# TouScruino-v2_1.net
KiCad netlist of a schematic drawn in EAGLE
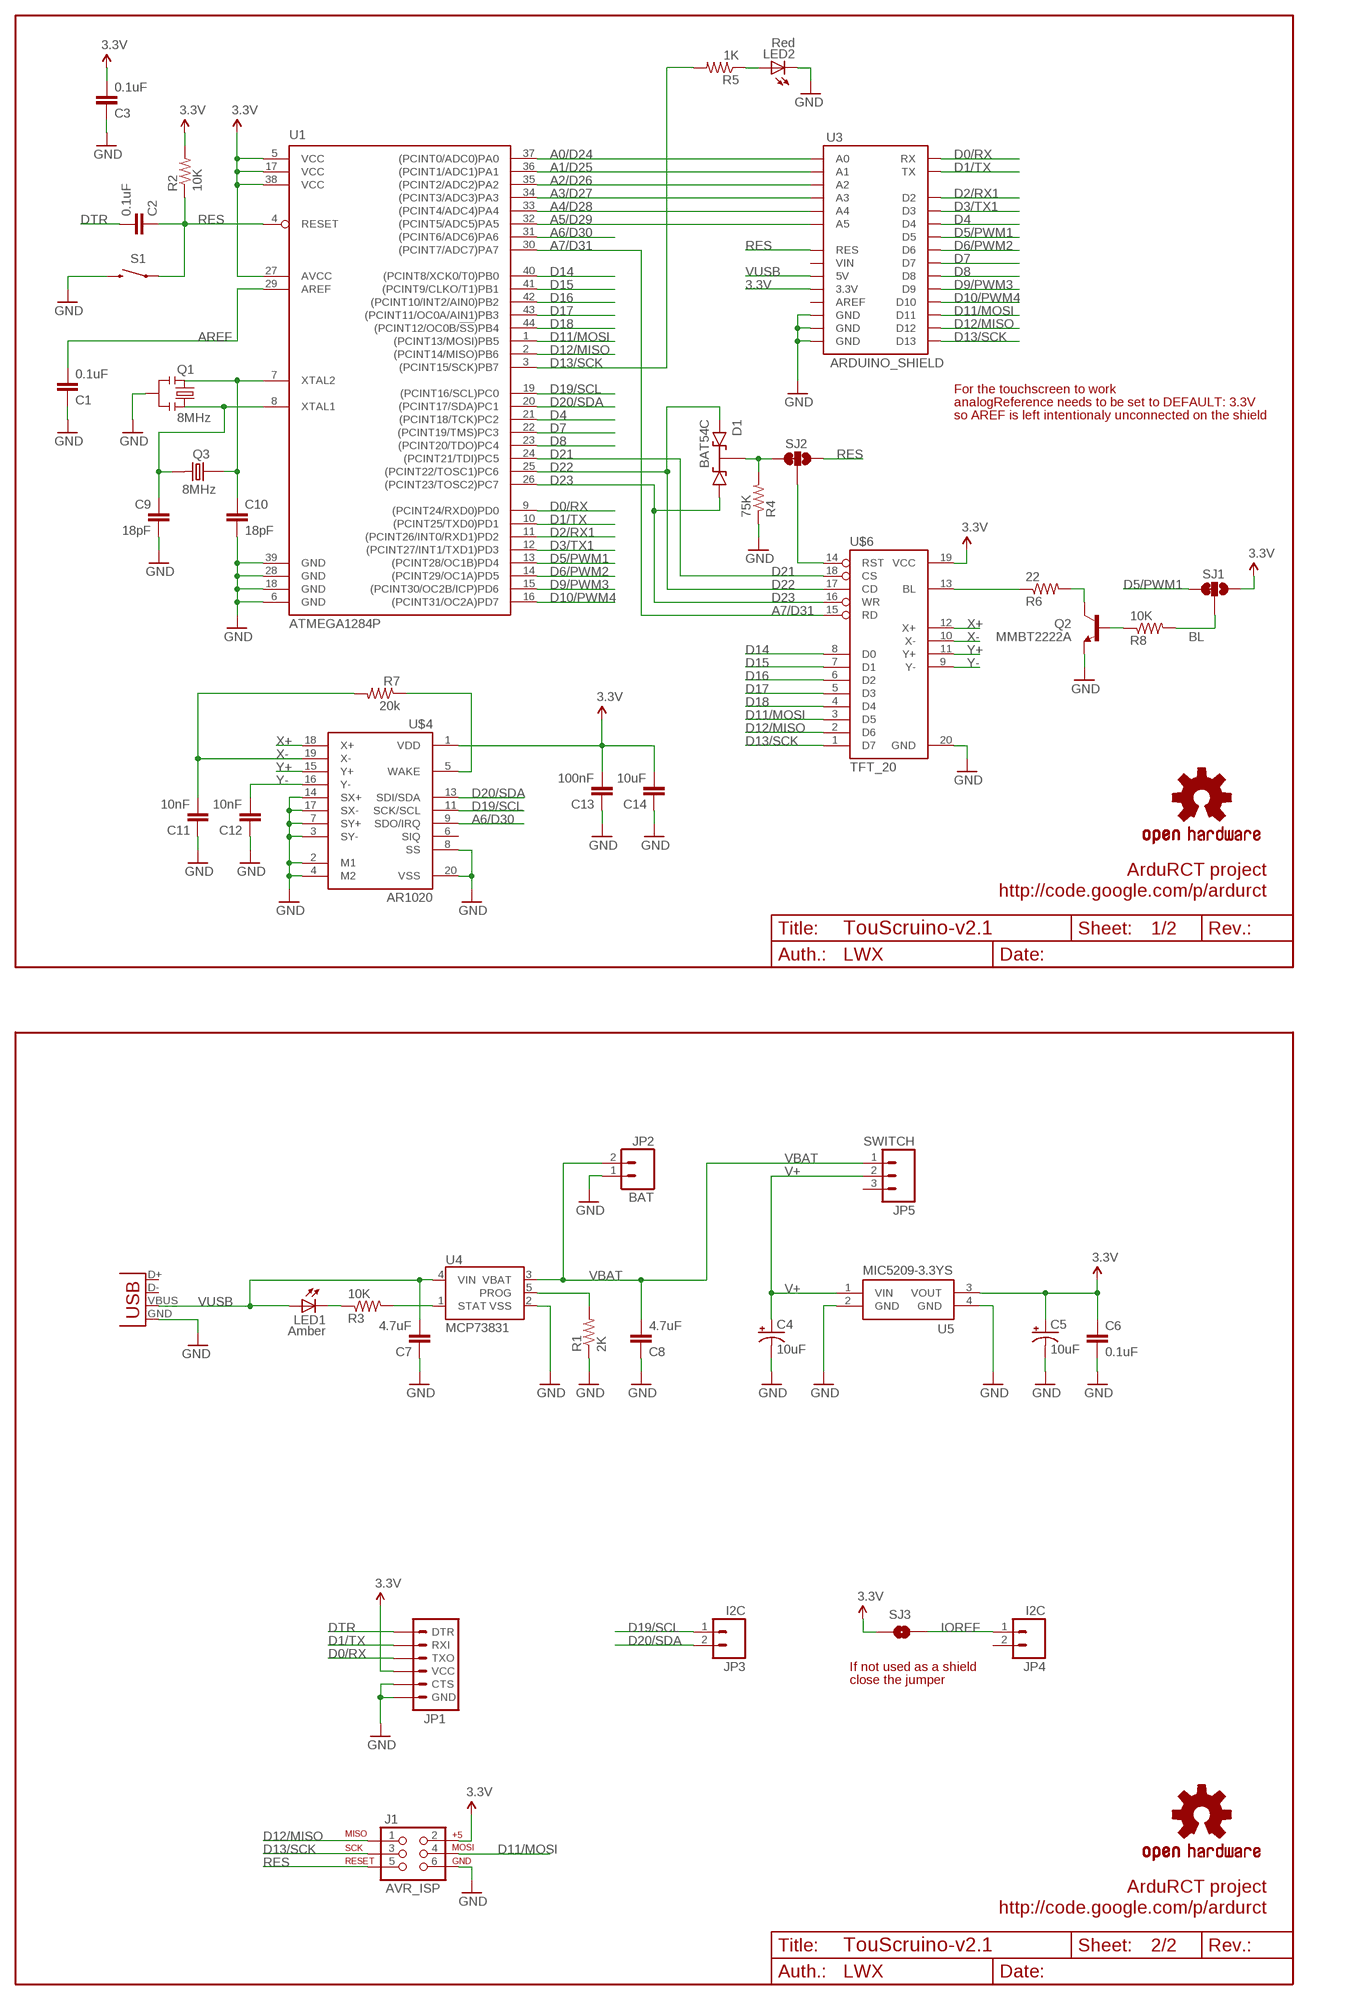
[diagram p0: schematic, sheet 1]

(export (version "E")
  (design (tool "Eeschema 10.0.6"))
  (components
    (comp (ref "C1")
      (value "0.1uF")
      (footprint "eagle-import:0805")
      (libsource (lib "eagle-import") (part "CAP0805"))
    )
    (comp (ref "C2")
      (value "0.1uF")
      (footprint "eagle-import:0805")
      (libsource (lib "eagle-import") (part "CAP0805"))
    )
    (comp (ref "C3")
      (value "0.1uF")
      (footprint "eagle-import:0805")
      (libsource (lib "eagle-import") (part "CAP0805"))
    )
    (comp (ref "C4")
      (value "10uF")
      (footprint "eagle-import:EIA3216")
      (libsource (lib "eagle-import") (part "CAP_POL1206"))
    )
    (comp (ref "C5")
      (value "10uF")
      (footprint "eagle-import:EIA3216")
      (libsource (lib "eagle-import") (part "CAP_POL1206"))
    )
    (comp (ref "C6")
      (value "0.1uF")
      (footprint "eagle-import:0805")
      (libsource (lib "eagle-import") (part "CAP0805"))
    )
    (comp (ref "C7")
      (value "4.7uF")
      (footprint "eagle-import:0805")
      (libsource (lib "eagle-import") (part "CAP0805"))
    )
    (comp (ref "C8")
      (value "4.7uF")
      (footprint "eagle-import:0805")
      (libsource (lib "eagle-import") (part "CAP0805"))
    )
    (comp (ref "C9")
      (value "18pF")
      (footprint "eagle-import:0603-CAP")
      (libsource (lib "eagle-import") (part "CAP0603-CAP"))
    )
    (comp (ref "C10")
      (value "18pF")
      (footprint "eagle-import:0603-CAP")
      (libsource (lib "eagle-import") (part "CAP0603-CAP"))
    )
    (comp (ref "C11")
      (value "10nF")
      (footprint "eagle-import:0805")
      (libsource (lib "eagle-import") (part "CAP0805"))
    )
    (comp (ref "C12")
      (value "10nF")
      (footprint "eagle-import:0805")
      (libsource (lib "eagle-import") (part "CAP0805"))
    )
    (comp (ref "C13")
      (value "100nF")
      (footprint "eagle-import:0805")
      (libsource (lib "eagle-import") (part "CAP0805"))
    )
    (comp (ref "C14")
      (value "10uF")
      (footprint "eagle-import:0805")
      (libsource (lib "eagle-import") (part "CAP0805"))
    )
    (comp (ref "D1")
      (value "BAT54C")
      (footprint "eagle-import:SOT23-3")
      (libsource (lib "eagle-import") (part "BAT54C"))
    )
    (comp (ref "J1")
      (value "AVR_ISP")
      (footprint "eagle-import:2X3")
      (libsource (lib "eagle-import") (part "AVR_SPI_PRG_6PTH"))
    )
    (comp (ref "JP1")
      (value "ARDUINO_SERIAL_PROGRAMPTH")
      (footprint "eagle-import:1X06")
      (libsource (lib "eagle-import") (part "ARDUINO_SERIAL_PROGRAMPTH"))
    )
    (comp (ref "JP2")
      (value "BAT")
      (footprint "eagle-import:JST-2-SMD")
      (libsource (lib "eagle-import") (part "M02-JST-2MM-SMT"))
    )
    (comp (ref "JP3")
      (value "I2C")
      (footprint "eagle-import:1X02")
      (libsource (lib "eagle-import") (part "M02"))
    )
    (comp (ref "JP4")
      (value "I2C")
      (footprint "eagle-import:1X02")
      (libsource (lib "eagle-import") (part "M02"))
    )
    (comp (ref "JP5")
      (value "SWITCH")
      (footprint "eagle-import:1X3_LONGPAD")
      (libsource (lib "eagle-import") (part "M03"))
    )
    (comp (ref "LED1")
      (value "Amber")
      (footprint "eagle-import:LED")
      (libsource (lib "eagle-import") (part "LED"))
    )
    (comp (ref "LED2")
      (value "Red")
      (footprint "eagle-import:LED-0805")
      (libsource (lib "eagle-import") (part "LED805"))
    )
    (comp (ref "Q1")
      (value "8MHz")
      (footprint "eagle-import:RESONATOR-SMD")
      (libsource (lib "eagle-import") (part "RESONATORSMD"))
    )
    (comp (ref "Q2")
      (value "MMBT2222A")
      (footprint "eagle-import:SOT23-3")
      (libsource (lib "eagle-import") (part "TRANSISTOR_NPNSOT23-3"))
    )
    (comp (ref "Q3")
      (value "8MHz")
      (footprint "eagle-import:CRYSTAL_5X3.2")
      (libsource (lib "eagle-import") (part "CRYSTAL_5X3.2"))
    )
    (comp (ref "R1")
      (value "2K")
      (footprint "eagle-import:0805")
      (libsource (lib "eagle-import") (part "RESISTOR0805-RES"))
    )
    (comp (ref "R2")
      (value "10K")
      (footprint "eagle-import:0805")
      (libsource (lib "eagle-import") (part "RESISTOR0805-RES"))
    )
    (comp (ref "R3")
      (value "10K")
      (footprint "eagle-import:0805")
      (libsource (lib "eagle-import") (part "RESISTOR0805-RES"))
    )
    (comp (ref "R4")
      (value "75K")
      (footprint "eagle-import:0805")
      (libsource (lib "eagle-import") (part "RESISTOR0805-RES"))
    )
    (comp (ref "R5")
      (value "1K")
      (footprint "eagle-import:0805")
      (libsource (lib "eagle-import") (part "RESISTOR0805-RES"))
    )
    (comp (ref "R6")
      (value "22")
      (footprint "eagle-import:0805")
      (libsource (lib "eagle-import") (part "RESISTOR0805-RES"))
    )
    (comp (ref "R7")
      (value "20k")
      (footprint "eagle-import:0805")
      (libsource (lib "eagle-import") (part "RESISTOR0805-RES"))
    )
    (comp (ref "R8")
      (value "10K")
      (footprint "eagle-import:0805")
      (libsource (lib "eagle-import") (part "RESISTOR0805-RES"))
    )
    (comp (ref "S1")
      (value "SWITCH-MOMENTARY-2SMD")
      (footprint "eagle-import:TACTILE_SWITCH_SMD")
      (libsource (lib "eagle-import") (part "SWITCH-MOMENTARY-2SMD"))
    )
    (comp (ref "SJ1")
      (value "SJ_2WAYS_1-2")
      (footprint "eagle-import:SJ_2WAYS_1-2_S")
      (libsource (lib "eagle-import") (part "SJ_2WAYS_1-2"))
    )
    (comp (ref "SJ2")
      (value "SJ_2WAYS_1-2")
      (footprint "eagle-import:SJ_2WAYS_1-2_S")
      (libsource (lib "eagle-import") (part "SJ_2WAYS_1-2"))
    )
    (comp (ref "SJ3")
      (value "SOLDERJUMPERNO")
      (footprint "eagle-import:SJ_2S-NO")
      (libsource (lib "eagle-import") (part "SOLDERJUMPERNO"))
    )
    (comp (ref "U$3")
      (value "OSHW-LOGOM")
      (footprint "eagle-import:OSHW-LOGO-M")
      (libsource (lib "eagle-import") (part "OSHW-LOGOM"))
    )
    (comp (ref "U$4")
      (value "AR1020")
      (footprint "eagle-import:SSOP20")
      (libsource (lib "eagle-import") (part "AR1020"))
    )
    (comp (ref "U$5")
      (value "OSHW-LOGOM")
      (footprint "eagle-import:OSHW-LOGO-M")
      (libsource (lib "eagle-import") (part "OSHW-LOGOM"))
    )
    (comp (ref "U$6")
      (value "TFT_20")
      (footprint "eagle-import:1X20")
      (libsource (lib "eagle-import") (part "TFT_20"))
    )
    (comp (ref "U1")
      (value "ATMEGA1284P")
      (footprint "eagle-import:TQFP44")
      (libsource (lib "eagle-import") (part "ATMEGA324A"))
    )
    (comp (ref "U3")
      (value "ARDUINO_SHIELD")
      (footprint "eagle-import:ARDUINO_SHIELD")
      (libsource (lib "eagle-import") (part "ARDUINO_SHIELD"))
    )
    (comp (ref "U4")
      (value "MCP73831")
      (footprint "eagle-import:SOT23-5")
      (libsource (lib "eagle-import") (part "MCP73831"))
    )
    (comp (ref "U5")
      (value "MIC5209-3.3YS")
      (footprint "eagle-import:SOT223")
      (libsource (lib "eagle-import") (part "MIC5209"))
    )
    (comp (ref "X2")
      (value "USB-MICROB")
      (footprint "eagle-import:USB-MICROB")
      (libsource (lib "eagle-import") (part "USB-MICROB"))
    )
  )
  (nets
    (net (code "1") (name "/A0{slash}D24") (class "Default")
      (node (ref "U1") (pin "37") (pinfunction "(PCINT0/ADC0)PA0_37") (pintype "bidirectional"))
      (node (ref "U3") (pin "A0") (pinfunction "A0_A0") (pintype "bidirectional"))
    )
    (net (code "2") (name "/A1{slash}D25") (class "Default")
      (node (ref "U1") (pin "36") (pinfunction "(PCINT1/ADC1)PA1_36") (pintype "bidirectional"))
      (node (ref "U3") (pin "A1") (pinfunction "A1_A1") (pintype "bidirectional"))
    )
    (net (code "3") (name "/A2{slash}D26") (class "Default")
      (node (ref "U1") (pin "35") (pinfunction "(PCINT2/ADC2)PA2_35") (pintype "bidirectional"))
      (node (ref "U3") (pin "A2") (pinfunction "A2_A2") (pintype "bidirectional"))
    )
    (net (code "4") (name "/A3{slash}D27") (class "Default")
      (node (ref "U1") (pin "34") (pinfunction "(PCINT3/ADC3)PA3_34") (pintype "bidirectional"))
      (node (ref "U3") (pin "A3") (pinfunction "A3_A3") (pintype "bidirectional"))
    )
    (net (code "5") (name "/A4{slash}D28") (class "Default")
      (node (ref "U1") (pin "33") (pinfunction "(PCINT4/ADC4)PA4_33") (pintype "bidirectional"))
      (node (ref "U3") (pin "A4") (pinfunction "A4_A4") (pintype "bidirectional"))
    )
    (net (code "6") (name "/A5{slash}D29") (class "Default")
      (node (ref "U1") (pin "32") (pinfunction "(PCINT5/ADC5)PA5_32") (pintype "bidirectional"))
      (node (ref "U3") (pin "A5") (pinfunction "A5_A5") (pintype "bidirectional"))
    )
    (net (code "7") (name "/A6{slash}D30") (class "Default")
      (node (ref "U$4") (pin "9") (pinfunction "SDO/IRQ_9") (pintype "bidirectional"))
      (node (ref "U1") (pin "31") (pinfunction "(PCINT6/ADC6)PA6_31") (pintype "bidirectional"))
    )
    (net (code "8") (name "/A7{slash}D31") (class "Default")
      (node (ref "U$6") (pin "15") (pinfunction "RD_15") (pintype "bidirectional"))
      (node (ref "U1") (pin "30") (pinfunction "(PCINT7/ADC7)PA7_30") (pintype "bidirectional"))
    )
    (net (code "9") (name "/AREF") (class "Default")
      (node (ref "C1") (pin "2") (pinfunction "2_2") (pintype "passive"))
      (node (ref "U1") (pin "29") (pinfunction "AREF_29") (pintype "passive"))
    )
    (net (code "10") (name "/BL") (class "Default")
      (node (ref "R8") (pin "2") (pinfunction "2_2") (pintype "passive"))
      (node (ref "SJ1") (pin "2") (pinfunction "2_2") (pintype "passive"))
    )
    (net (code "11") (name "/D0{slash}RX") (class "Default")
      (node (ref "JP1") (pin "3") (pinfunction "TXO_3") (pintype "passive"))
      (node (ref "U1") (pin "9") (pinfunction "(PCINT24/RXD0)PD0_9") (pintype "bidirectional"))
      (node (ref "U3") (pin "RX") (pinfunction "RX_RX") (pintype "bidirectional"))
    )
    (net (code "12") (name "/D1{slash}TX") (class "Default")
      (node (ref "JP1") (pin "2") (pinfunction "RXI_2") (pintype "passive"))
      (node (ref "U1") (pin "10") (pinfunction "(PCINT25/TXD0)PD1_10") (pintype "bidirectional"))
      (node (ref "U3") (pin "TX") (pinfunction "TX_TX") (pintype "bidirectional"))
    )
    (net (code "13") (name "/D2{slash}RX1") (class "Default")
      (node (ref "U1") (pin "11") (pinfunction "(PCINT26/INT0/RXD1)PD2_11") (pintype "bidirectional"))
      (node (ref "U3") (pin "D2") (pinfunction "D2_D2") (pintype "bidirectional"))
    )
    (net (code "14") (name "/D3{slash}TX1") (class "Default")
      (node (ref "U1") (pin "12") (pinfunction "(PCINT27/INT1/TXD1)PD3_12") (pintype "bidirectional"))
      (node (ref "U3") (pin "D3") (pinfunction "D3_D3") (pintype "bidirectional"))
    )
    (net (code "15") (name "/D4") (class "Default")
      (node (ref "U1") (pin "21") (pinfunction "(PCINT18/TCK)PC2_21") (pintype "output"))
      (node (ref "U3") (pin "D4") (pinfunction "D4_D4") (pintype "bidirectional"))
    )
    (net (code "16") (name "/D5{slash}PWM1") (class "Default")
      (node (ref "SJ1") (pin "1") (pinfunction "1_1") (pintype "passive"))
      (node (ref "U1") (pin "13") (pinfunction "(PCINT28/OC1B)PD4_13") (pintype "bidirectional"))
      (node (ref "U3") (pin "D5") (pinfunction "D5_D5") (pintype "bidirectional"))
    )
    (net (code "17") (name "/D6{slash}PWM2") (class "Default")
      (node (ref "U1") (pin "14") (pinfunction "(PCINT29/OC1A)PD5_14") (pintype "bidirectional"))
      (node (ref "U3") (pin "D6") (pinfunction "D6_D6") (pintype "bidirectional"))
    )
    (net (code "18") (name "/D7") (class "Default")
      (node (ref "U1") (pin "22") (pinfunction "(PCINT19/TMS)PC3_22") (pintype "output"))
      (node (ref "U3") (pin "D7") (pinfunction "D7_D7") (pintype "bidirectional"))
    )
    (net (code "19") (name "/D8") (class "Default")
      (node (ref "U1") (pin "23") (pinfunction "(PCINT20/TDO)PC4_23") (pintype "output"))
      (node (ref "U3") (pin "D8") (pinfunction "D8_D8") (pintype "bidirectional"))
    )
    (net (code "20") (name "/D9{slash}PWM3") (class "Default")
      (node (ref "U1") (pin "15") (pinfunction "(PCINT30/OC2B/ICP)PD6_15") (pintype "bidirectional"))
      (node (ref "U3") (pin "D9") (pinfunction "D9_D9") (pintype "bidirectional"))
    )
    (net (code "21") (name "/D10{slash}PWM4") (class "Default")
      (node (ref "U1") (pin "16") (pinfunction "(PCINT31/OC2A)PD7_16") (pintype "bidirectional"))
      (node (ref "U3") (pin "D10") (pinfunction "D10_D10") (pintype "bidirectional"))
    )
    (net (code "22") (name "/D11{slash}MOSI") (class "Default")
      (node (ref "J1") (pin "4") (pinfunction "4_4") (pintype "passive"))
      (node (ref "U$6") (pin "3") (pinfunction "D5_3") (pintype "bidirectional"))
      (node (ref "U1") (pin "1") (pinfunction "(PCINT13/MOSI)PB5_1") (pintype "bidirectional"))
      (node (ref "U3") (pin "D11") (pinfunction "D11_D11") (pintype "bidirectional"))
    )
    (net (code "23") (name "/D12{slash}MISO") (class "Default")
      (node (ref "J1") (pin "1") (pinfunction "1_1") (pintype "passive"))
      (node (ref "U$6") (pin "2") (pinfunction "D6_2") (pintype "bidirectional"))
      (node (ref "U1") (pin "2") (pinfunction "(PCINT14/MISO)PB6_2") (pintype "bidirectional"))
      (node (ref "U3") (pin "D12") (pinfunction "D12_D12") (pintype "bidirectional"))
    )
    (net (code "24") (name "/D13{slash}SCK") (class "Default")
      (node (ref "J1") (pin "3") (pinfunction "3_3") (pintype "passive"))
      (node (ref "R5") (pin "2") (pinfunction "2_2") (pintype "passive"))
      (node (ref "U$6") (pin "1") (pinfunction "D7_1") (pintype "bidirectional"))
      (node (ref "U1") (pin "3") (pinfunction "(PCINT15/SCK)PB7_3") (pintype "bidirectional"))
      (node (ref "U3") (pin "D13") (pinfunction "D13_D13") (pintype "bidirectional"))
    )
    (net (code "25") (name "/D14") (class "Default")
      (node (ref "U$6") (pin "8") (pinfunction "D0_8") (pintype "bidirectional"))
      (node (ref "U1") (pin "40") (pinfunction "(PCINT8/XCK0/T0)PB0_40") (pintype "bidirectional"))
    )
    (net (code "26") (name "/D15") (class "Default")
      (node (ref "U$6") (pin "7") (pinfunction "D1_7") (pintype "bidirectional"))
      (node (ref "U1") (pin "41") (pinfunction "(PCINT9/CLKO/T1)PB1_41") (pintype "bidirectional"))
    )
    (net (code "27") (name "/D16") (class "Default")
      (node (ref "U$6") (pin "6") (pinfunction "D2_6") (pintype "bidirectional"))
      (node (ref "U1") (pin "42") (pinfunction "(PCINT10/INT2/AIN0)PB2_42") (pintype "bidirectional"))
    )
    (net (code "28") (name "/D17") (class "Default")
      (node (ref "U$6") (pin "5") (pinfunction "D3_5") (pintype "bidirectional"))
      (node (ref "U1") (pin "43") (pinfunction "(PCINT11/OC0A/AIN1)PB3_43") (pintype "bidirectional"))
    )
    (net (code "29") (name "/D18") (class "Default")
      (node (ref "U$6") (pin "4") (pinfunction "D4_4") (pintype "bidirectional"))
      (node (ref "U1") (pin "44") (pinfunction "(PCINT12/OC0B/~{SS})PB4_44") (pintype "bidirectional"))
    )
    (net (code "30") (name "/D19{slash}SCL") (class "Default")
      (node (ref "JP3") (pin "1") (pinfunction "1_1") (pintype "passive"))
      (node (ref "U$4") (pin "11") (pinfunction "SCK/SCL_11") (pintype "bidirectional"))
      (node (ref "U1") (pin "19") (pinfunction "(PCINT16/SCL)PC0_19") (pintype "output"))
    )
    (net (code "31") (name "/D20{slash}SDA") (class "Default")
      (node (ref "JP3") (pin "2") (pinfunction "2_2") (pintype "passive"))
      (node (ref "U$4") (pin "13") (pinfunction "SDI/SDA_13") (pintype "bidirectional"))
      (node (ref "U1") (pin "20") (pinfunction "(PCINT17/SDA)PC1_20") (pintype "output"))
    )
    (net (code "32") (name "/D21") (class "Default")
      (node (ref "U$6") (pin "18") (pinfunction "CS_18") (pintype "bidirectional"))
      (node (ref "U1") (pin "24") (pinfunction "(PCINT21/TDI)PC5_24") (pintype "output"))
    )
    (net (code "33") (name "/D22") (class "Default")
      (node (ref "D1") (pin "2") (pinfunction "A2_2") (pintype "bidirectional"))
      (node (ref "U$6") (pin "17") (pinfunction "CD_17") (pintype "bidirectional"))
      (node (ref "U1") (pin "25") (pinfunction "(PCINT22/TOSC1)PC6_25") (pintype "output"))
    )
    (net (code "34") (name "/D23") (class "Default")
      (node (ref "D1") (pin "1") (pinfunction "A1_1") (pintype "bidirectional"))
      (node (ref "U$6") (pin "16") (pinfunction "WR_16") (pintype "bidirectional"))
      (node (ref "U1") (pin "26") (pinfunction "(PCINT23/TOSC2)PC7_26") (pintype "output"))
    )
    (net (code "35") (name "/DTR") (class "Default")
      (node (ref "C2") (pin "2") (pinfunction "2_2") (pintype "passive"))
      (node (ref "JP1") (pin "1") (pinfunction "DTR_1") (pintype "passive"))
    )
    (net (code "36") (name "/IOREF") (class "Default")
      (node (ref "JP4") (pin "1") (pinfunction "1_1") (pintype "passive"))
      (node (ref "SJ3") (pin "2") (pinfunction "2_2") (pintype "passive"))
    )
    (net (code "37") (name "/RES") (class "Default")
      (node (ref "C2") (pin "1") (pinfunction "1_1") (pintype "passive"))
      (node (ref "J1") (pin "5") (pinfunction "5_5") (pintype "passive"))
      (node (ref "R2") (pin "1") (pinfunction "1_1") (pintype "passive"))
      (node (ref "S1") (pin "1") (pinfunction "1_1") (pintype "passive"))
      (node (ref "SJ2") (pin "3") (pinfunction "3_3") (pintype "passive"))
      (node (ref "U1") (pin "4") (pinfunction "RESET_4") (pintype "input"))
      (node (ref "U3") (pin "RES") (pinfunction "RES_RES") (pintype "bidirectional"))
    )
    (net (code "38") (name "/V+") (class "Default")
      (node (ref "C4") (pin "A") (pinfunction "+_A") (pintype "passive"))
      (node (ref "JP5") (pin "2") (pinfunction "2_2") (pintype "passive"))
      (node (ref "U5") (pin "1") (pinfunction "VIN_1") (pintype "bidirectional"))
    )
    (net (code "39") (name "/VBAT") (class "Default")
      (node (ref "C8") (pin "2") (pinfunction "2_2") (pintype "passive"))
      (node (ref "JP2") (pin "2") (pinfunction "2_2") (pintype "passive"))
      (node (ref "JP5") (pin "1") (pinfunction "1_1") (pintype "passive"))
      (node (ref "U4") (pin "3") (pinfunction "VBAT_3") (pintype "power_in"))
    )
    (net (code "40") (name "/VUSB") (class "Default")
      (node (ref "C7") (pin "2") (pinfunction "2_2") (pintype "passive"))
      (node (ref "LED1") (pin "A1") (pinfunction "A_A1") (pintype "passive"))
      (node (ref "U3") (pin "5V") (pinfunction "5V_5V") (pintype "bidirectional"))
      (node (ref "U4") (pin "4") (pinfunction "VIN_4") (pintype "power_in"))
      (node (ref "X2") (pin "VBUS") (pinfunction "VBUS_VBUS") (pintype "bidirectional"))
    )
    (net (code "41") (name "/X+") (class "Default")
      (node (ref "U$4") (pin "18") (pinfunction "X+_18") (pintype "bidirectional"))
      (node (ref "U$6") (pin "12") (pinfunction "X+_12") (pintype "bidirectional"))
    )
    (net (code "42") (name "/X-") (class "Default")
      (node (ref "C11") (pin "2") (pinfunction "2_2") (pintype "passive"))
      (node (ref "R7") (pin "2") (pinfunction "2_2") (pintype "passive"))
      (node (ref "U$4") (pin "19") (pinfunction "X-_19") (pintype "bidirectional"))
      (node (ref "U$6") (pin "10") (pinfunction "X-_10") (pintype "bidirectional"))
    )
    (net (code "43") (name "/Y+") (class "Default")
      (node (ref "U$4") (pin "15") (pinfunction "Y+_15") (pintype "bidirectional"))
      (node (ref "U$6") (pin "11") (pinfunction "Y+_11") (pintype "bidirectional"))
    )
    (net (code "44") (name "/Y-") (class "Default")
      (node (ref "C12") (pin "2") (pinfunction "2_2") (pintype "passive"))
      (node (ref "U$4") (pin "16") (pinfunction "Y-_16") (pintype "bidirectional"))
      (node (ref "U$6") (pin "9") (pinfunction "Y-_9") (pintype "bidirectional"))
    )
    (net (code "45") (name "3.3V") (class "Default")
      (node (ref "C13") (pin "2") (pinfunction "2_2") (pintype "passive"))
      (node (ref "C14") (pin "2") (pinfunction "2_2") (pintype "passive"))
      (node (ref "C3") (pin "2") (pinfunction "2_2") (pintype "passive"))
      (node (ref "C5") (pin "A") (pinfunction "+_A") (pintype "passive"))
      (node (ref "C6") (pin "1") (pinfunction "1_1") (pintype "passive"))
      (node (ref "J1") (pin "2") (pinfunction "2_2") (pintype "passive"))
      (node (ref "JP1") (pin "4") (pinfunction "VCC_4") (pintype "passive"))
      (node (ref "R2") (pin "2") (pinfunction "2_2") (pintype "passive"))
      (node (ref "SJ1") (pin "3") (pinfunction "3_3") (pintype "passive"))
      (node (ref "SJ3") (pin "1") (pinfunction "1_1") (pintype "passive"))
      (node (ref "U$4") (pin "1") (pinfunction "VDD_1") (pintype "bidirectional"))
      (node (ref "U$6") (pin "19") (pinfunction "VCC_19") (pintype "bidirectional"))
      (node (ref "U1") (pin "17") (pinfunction "VCC_17") (pintype "power_in"))
      (node (ref "U1") (pin "27") (pinfunction "AVCC_27") (pintype "power_in"))
      (node (ref "U1") (pin "38") (pinfunction "VCC_38") (pintype "power_in"))
      (node (ref "U1") (pin "5") (pinfunction "VCC_5") (pintype "power_in"))
      (node (ref "U3") (pin "3.3V") (pinfunction "3.3V_3.3V") (pintype "bidirectional"))
      (node (ref "U5") (pin "3") (pinfunction "VOUT_3") (pintype "bidirectional"))
    )
    (net (code "46") (name "GND") (class "Default")
      (node (ref "C1") (pin "1") (pinfunction "1_1") (pintype "passive"))
      (node (ref "C10") (pin "2") (pinfunction "2_2") (pintype "passive"))
      (node (ref "C11") (pin "1") (pinfunction "1_1") (pintype "passive"))
      (node (ref "C12") (pin "1") (pinfunction "1_1") (pintype "passive"))
      (node (ref "C13") (pin "1") (pinfunction "1_1") (pintype "passive"))
      (node (ref "C14") (pin "1") (pinfunction "1_1") (pintype "passive"))
      (node (ref "C3") (pin "1") (pinfunction "1_1") (pintype "passive"))
      (node (ref "C4") (pin "C") (pinfunction "-_C") (pintype "passive"))
      (node (ref "C5") (pin "C") (pinfunction "-_C") (pintype "passive"))
      (node (ref "C6") (pin "2") (pinfunction "2_2") (pintype "passive"))
      (node (ref "C7") (pin "1") (pinfunction "1_1") (pintype "passive"))
      (node (ref "C8") (pin "1") (pinfunction "1_1") (pintype "passive"))
      (node (ref "C9") (pin "2") (pinfunction "2_2") (pintype "passive"))
      (node (ref "J1") (pin "6") (pinfunction "6_6") (pintype "passive"))
      (node (ref "JP1") (pin "5") (pinfunction "CTS_5") (pintype "passive"))
      (node (ref "JP1") (pin "6") (pinfunction "GND_6") (pintype "passive"))
      (node (ref "JP2") (pin "1") (pinfunction "1_1") (pintype "passive"))
      (node (ref "LED2") (pin "2") (pinfunction "C_2") (pintype "passive"))
      (node (ref "Q1") (pin "2") (pinfunction "2_2") (pintype "passive"))
      (node (ref "Q2") (pin "2") (pinfunction "E_2") (pintype "passive"))
      (node (ref "R1") (pin "1") (pinfunction "1_1") (pintype "passive"))
      (node (ref "R4") (pin "1") (pinfunction "1_1") (pintype "passive"))
      (node (ref "S1") (pin "3") (pinfunction "2_3") (pintype "passive"))
      (node (ref "U$4") (pin "14") (pinfunction "SX+_14") (pintype "bidirectional"))
      (node (ref "U$4") (pin "17") (pinfunction "SX-_17") (pintype "bidirectional"))
      (node (ref "U$4") (pin "2") (pinfunction "M1_2") (pintype "bidirectional"))
      (node (ref "U$4") (pin "20") (pinfunction "VSS_20") (pintype "bidirectional"))
      (node (ref "U$4") (pin "3") (pinfunction "SY-_3") (pintype "bidirectional"))
      (node (ref "U$4") (pin "4") (pinfunction "M2_4") (pintype "bidirectional"))
      (node (ref "U$4") (pin "7") (pinfunction "SY+_7") (pintype "bidirectional"))
      (node (ref "U$4") (pin "8") (pinfunction "SS_8") (pintype "bidirectional"))
      (node (ref "U$6") (pin "20") (pinfunction "GND_20") (pintype "bidirectional"))
      (node (ref "U1") (pin "18") (pinfunction "GND_18") (pintype "power_in"))
      (node (ref "U1") (pin "28") (pinfunction "GND_28") (pintype "power_in"))
      (node (ref "U1") (pin "39") (pinfunction "GND_39") (pintype "power_in"))
      (node (ref "U1") (pin "6") (pinfunction "GND_6") (pintype "power_in"))
      (node (ref "U3") (pin "GND@0") (pinfunction "GND_GND@0") (pintype "bidirectional"))
      (node (ref "U3") (pin "GND@1") (pinfunction "GND_GND@1") (pintype "bidirectional"))
      (node (ref "U3") (pin "GND@2") (pinfunction "GND_GND@2") (pintype "bidirectional"))
      (node (ref "U4") (pin "2") (pinfunction "VSS_2") (pintype "power_in"))
      (node (ref "U5") (pin "2") (pinfunction "GND_2") (pintype "bidirectional"))
      (node (ref "U5") (pin "4") (pinfunction "GND_4") (pintype "bidirectional"))
      (node (ref "X2") (pin "GND") (pinfunction "GND_GND") (pintype "bidirectional"))
    )
    (net (code "47") (name "Net-(D1-K)") (class "Default")
      (node (ref "D1") (pin "3") (pinfunction "K_3") (pintype "bidirectional"))
      (node (ref "R4") (pin "2") (pinfunction "2_2") (pintype "passive"))
      (node (ref "SJ2") (pin "1") (pinfunction "1_1") (pintype "passive"))
    )
    (net (code "48") (name "Net-(LED1-C)") (class "Default")
      (node (ref "LED1") (pin "C1") (pinfunction "C_C1") (pintype "passive"))
      (node (ref "R3") (pin "1") (pinfunction "1_1") (pintype "passive"))
    )
    (net (code "49") (name "Net-(LED2-A)") (class "Default")
      (node (ref "LED2") (pin "1") (pinfunction "A_1") (pintype "passive"))
      (node (ref "R5") (pin "1") (pinfunction "1_1") (pintype "passive"))
    )
    (net (code "50") (name "Net-(Q2-B)") (class "Default")
      (node (ref "Q2") (pin "1") (pinfunction "B_1") (pintype "passive"))
      (node (ref "R8") (pin "1") (pinfunction "1_1") (pintype "passive"))
    )
    (net (code "51") (name "Net-(Q2-C)") (class "Default")
      (node (ref "Q2") (pin "3") (pinfunction "C_3") (pintype "passive"))
      (node (ref "R6") (pin "2") (pinfunction "2_2") (pintype "passive"))
    )
    (net (code "52") (name "Net-(U$4-WAKE)") (class "Default")
      (node (ref "R7") (pin "1") (pinfunction "1_1") (pintype "passive"))
      (node (ref "U$4") (pin "5") (pinfunction "WAKE_5") (pintype "bidirectional"))
    )
    (net (code "53") (name "Net-(U$6-BL)") (class "Default")
      (node (ref "R6") (pin "1") (pinfunction "1_1") (pintype "passive"))
      (node (ref "U$6") (pin "13") (pinfunction "BL_13") (pintype "bidirectional"))
    )
    (net (code "54") (name "Net-(U$6-RST)") (class "Default")
      (node (ref "SJ2") (pin "2") (pinfunction "2_2") (pintype "passive"))
      (node (ref "U$6") (pin "14") (pinfunction "RST_14") (pintype "bidirectional"))
    )
    (net (code "55") (name "Net-(U1-XTAL1)") (class "Default")
      (node (ref "C9") (pin "1") (pinfunction "1_1") (pintype "passive"))
      (node (ref "Q1") (pin "1") (pinfunction "1_1") (pintype "passive"))
      (node (ref "Q3") (pin "2") (pinfunction "2_2") (pintype "passive"))
      (node (ref "U1") (pin "8") (pinfunction "XTAL1_8") (pintype "bidirectional"))
    )
    (net (code "56") (name "Net-(U1-XTAL2)") (class "Default")
      (node (ref "C10") (pin "1") (pinfunction "1_1") (pintype "passive"))
      (node (ref "Q1") (pin "3") (pinfunction "3_3") (pintype "passive"))
      (node (ref "Q3") (pin "1") (pinfunction "1_1") (pintype "passive"))
      (node (ref "U1") (pin "7") (pinfunction "XTAL2_7") (pintype "bidirectional"))
    )
    (net (code "57") (name "Net-(U4-PROG)") (class "Default")
      (node (ref "R1") (pin "2") (pinfunction "2_2") (pintype "passive"))
      (node (ref "U4") (pin "5") (pinfunction "PROG_5") (pintype "input"))
    )
    (net (code "58") (name "Net-(U4-STAT)") (class "Default")
      (node (ref "R3") (pin "2") (pinfunction "2_2") (pintype "passive"))
      (node (ref "U4") (pin "1") (pinfunction "STAT_1") (pintype "output"))
    )
    (net (code "59") (name "unconnected-(JP4-Pad2)") (class "Default")
      (node (ref "JP4") (pin "2") (pinfunction "2_2") (pintype "passive"))
    )
    (net (code "60") (name "unconnected-(JP5-Pad3)") (class "Default")
      (node (ref "JP5") (pin "3") (pinfunction "3_3") (pintype "passive"))
    )
    (net (code "61") (name "unconnected-(U$4-SIQ-Pad6)") (class "Default")
      (node (ref "U$4") (pin "6") (pinfunction "SIQ_6") (pintype "bidirectional"))
    )
    (net (code "62") (name "unconnected-(U3-PadAREF)") (class "Default")
      (node (ref "U3") (pin "AREF") (pinfunction "AREF_AREF") (pintype "bidirectional"))
    )
    (net (code "63") (name "unconnected-(U3-PadVIN)") (class "Default")
      (node (ref "U3") (pin "VIN") (pinfunction "VIN_VIN") (pintype "bidirectional"))
    )
    (net (code "64") (name "unconnected-(X2-PadD+)") (class "Default")
      (node (ref "X2") (pin "D+") (pinfunction "D+_D+") (pintype "bidirectional"))
    )
    (net (code "65") (name "unconnected-(X2-PadD-)") (class "Default")
      (node (ref "X2") (pin "D-") (pinfunction "D-_D-") (pintype "bidirectional"))
    )
  )
)
